# 3_valve.net
KiCad netlist of a schematic drawn in EAGLE
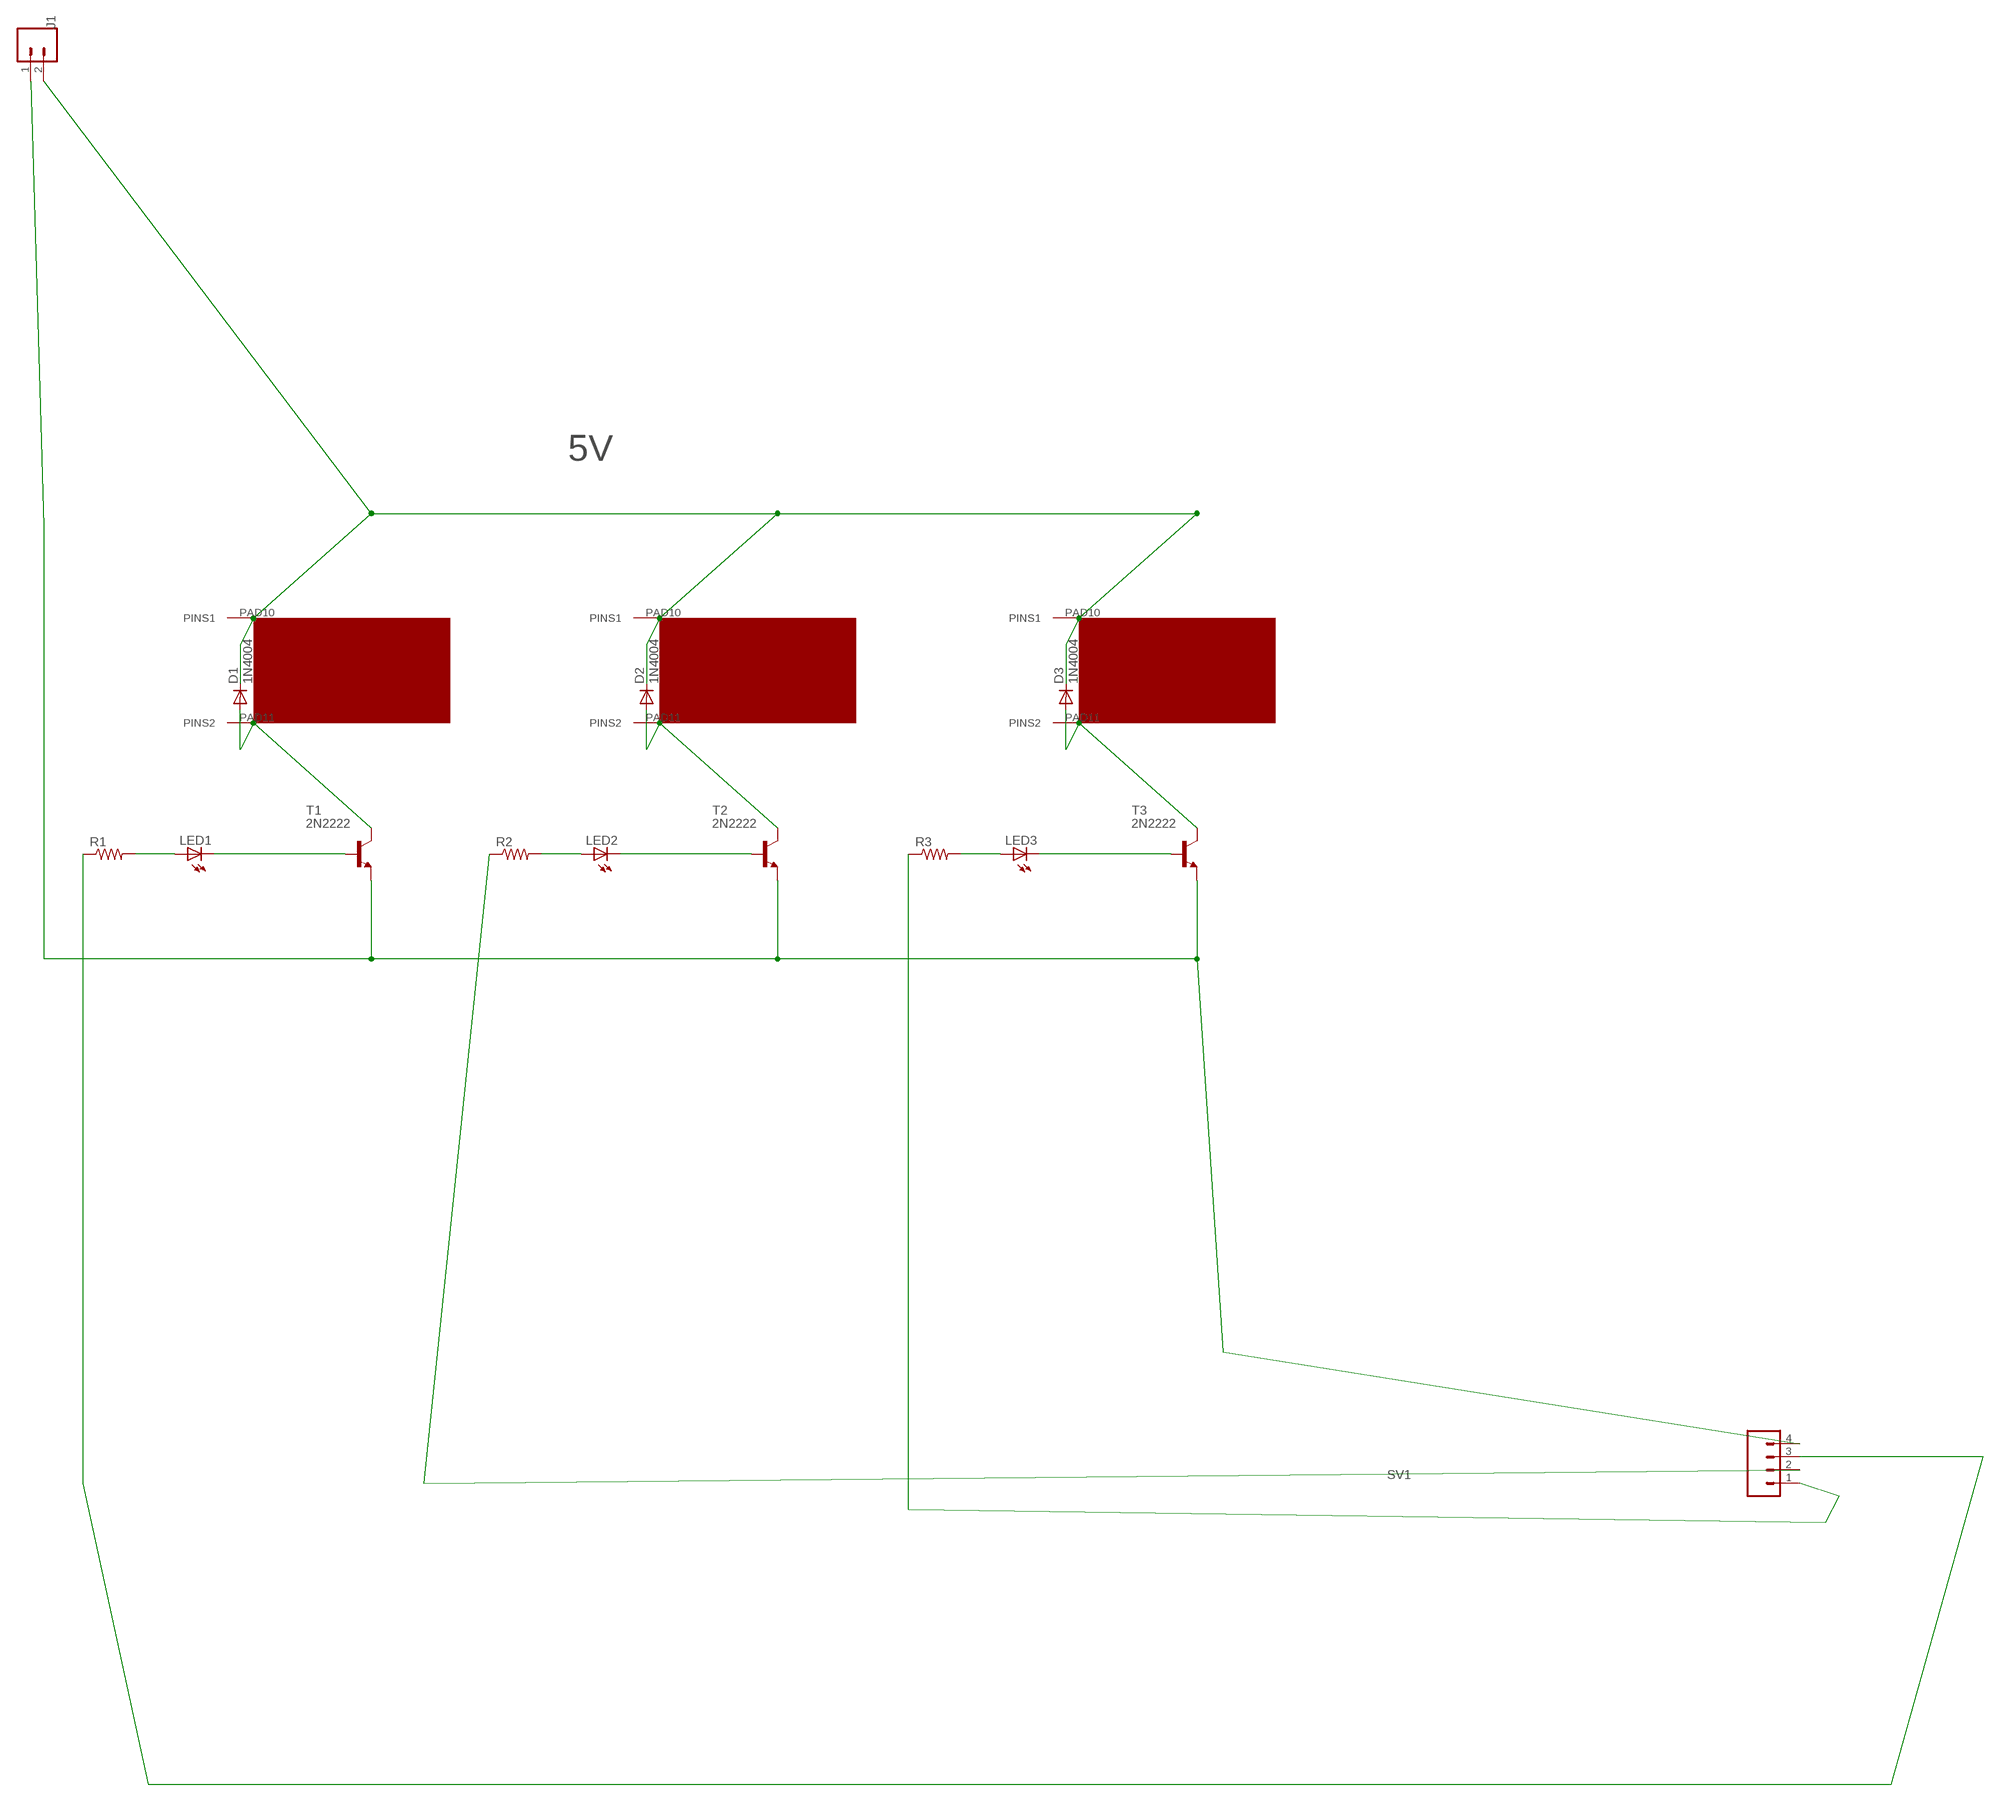
[diagram p0: schematic, sheet 1]

(export (version "E")
  (design (tool "Eeschema 10.0.6"))
  (components
    (comp (ref "D1")
      (value "1N4004")
      (footprint "eagle-import:DO41-10")
      (libsource (lib "eagle-import") (part "1N4004"))
    )
    (comp (ref "D2")
      (value "1N4004")
      (footprint "eagle-import:DO41-10")
      (libsource (lib "eagle-import") (part "1N4004"))
    )
    (comp (ref "D3")
      (value "1N4004")
      (footprint "eagle-import:DO41-10")
      (libsource (lib "eagle-import") (part "1N4004"))
    )
    (comp (ref "J1")
      (value "CONN_023.5MM")
      (footprint "eagle-import:SCREWTERMINAL-3.5MM-2")
      (libsource (lib "eagle-import") (part "CONN_023.5MM"))
    )
    (comp (ref "LED1")
      (value "LED5MM")
      (footprint "eagle-import:LED5MM")
      (libsource (lib "eagle-import") (part "LED5MM"))
    )
    (comp (ref "LED2")
      (value "LED5MM")
      (footprint "eagle-import:LED5MM")
      (libsource (lib "eagle-import") (part "LED5MM"))
    )
    (comp (ref "LED3")
      (value "LED5MM")
      (footprint "eagle-import:LED5MM")
      (libsource (lib "eagle-import") (part "LED5MM"))
    )
    (comp (ref "R1")
      (value "R-US_0207/10")
      (footprint "eagle-import:0207_10")
      (libsource (lib "eagle-import") (part "R-US_0207/10"))
    )
    (comp (ref "R2")
      (value "R-US_0207/10")
      (footprint "eagle-import:0207_10")
      (libsource (lib "eagle-import") (part "R-US_0207/10"))
    )
    (comp (ref "R3")
      (value "R-US_0207/10")
      (footprint "eagle-import:0207_10")
      (libsource (lib "eagle-import") (part "R-US_0207/10"))
    )
    (comp (ref "SV1")
      (value "CONN_04")
      (footprint "eagle-import:1X04")
      (libsource (lib "eagle-import") (part "CONN_04"))
    )
    (comp (ref "T1")
      (value "2N2222")
      (footprint "eagle-import:TO92-EBC-OVAL")
      (libsource (lib "eagle-import") (part "2N2222"))
    )
    (comp (ref "T2")
      (value "2N2222")
      (footprint "eagle-import:TO92-EBC-OVAL")
      (libsource (lib "eagle-import") (part "2N2222"))
    )
    (comp (ref "T3")
      (value "2N2222")
      (footprint "eagle-import:TO92-EBC-OVAL")
      (libsource (lib "eagle-import") (part "2N2222"))
    )
    (comp (ref "U$1")
      (value "VALVE")
      (footprint "eagle-import:VALVTEST2")
      (libsource (lib "eagle-import") (part "VALVE"))
    )
    (comp (ref "U$2")
      (value "VALVE")
      (footprint "eagle-import:VALVTEST2")
      (libsource (lib "eagle-import") (part "VALVE"))
    )
    (comp (ref "VALVE3")
      (value "VALVE")
      (footprint "eagle-import:VALVTEST2")
      (libsource (lib "eagle-import") (part "VALVE"))
    )
  )
  (nets
    (net (code "1") (name "/5V") (class "Default")
      (node (ref "D1") (pin "C") (pinfunction "C_C") (pintype "passive"))
      (node (ref "D2") (pin "C") (pinfunction "C_C") (pintype "passive"))
      (node (ref "D3") (pin "C") (pinfunction "C_C") (pintype "passive"))
      (node (ref "J1") (pin "2") (pinfunction "2_2") (pintype "passive"))
      (node (ref "U$1") (pin "PAD10") (pinfunction "PINS1_PAD10") (pintype "bidirectional"))
      (node (ref "U$2") (pin "PAD10") (pinfunction "PINS1_PAD10") (pintype "bidirectional"))
      (node (ref "VALVE3") (pin "PAD10") (pinfunction "PINS1_PAD10") (pintype "bidirectional"))
    )
    (net (code "2") (name "Net-(J1-Pad1)") (class "Default")
      (node (ref "J1") (pin "1") (pinfunction "1_1") (pintype "passive"))
      (node (ref "SV1") (pin "4") (pinfunction "4_4") (pintype "passive"))
      (node (ref "T1") (pin "E") (pinfunction "E_E") (pintype "passive"))
      (node (ref "T2") (pin "E") (pinfunction "E_E") (pintype "passive"))
      (node (ref "T3") (pin "E") (pinfunction "E_E") (pintype "passive"))
    )
    (net (code "3") (name "Net-(LED1-C)") (class "Default")
      (node (ref "LED1") (pin "K") (pinfunction "C_K") (pintype "passive"))
      (node (ref "T1") (pin "B") (pinfunction "B_B") (pintype "passive"))
    )
    (net (code "4") (name "Net-(LED1-PadA)") (class "Default")
      (node (ref "LED1") (pin "A") (pinfunction "A_A") (pintype "passive"))
      (node (ref "R1") (pin "2") (pinfunction "2_2") (pintype "passive"))
    )
    (net (code "5") (name "Net-(LED2-C)") (class "Default")
      (node (ref "LED2") (pin "K") (pinfunction "C_K") (pintype "passive"))
      (node (ref "T2") (pin "B") (pinfunction "B_B") (pintype "passive"))
    )
    (net (code "6") (name "Net-(LED2-PadA)") (class "Default")
      (node (ref "LED2") (pin "A") (pinfunction "A_A") (pintype "passive"))
      (node (ref "R2") (pin "2") (pinfunction "2_2") (pintype "passive"))
    )
    (net (code "7") (name "Net-(LED3-C)") (class "Default")
      (node (ref "LED3") (pin "K") (pinfunction "C_K") (pintype "passive"))
      (node (ref "T3") (pin "B") (pinfunction "B_B") (pintype "passive"))
    )
    (net (code "8") (name "Net-(LED3-PadA)") (class "Default")
      (node (ref "LED3") (pin "A") (pinfunction "A_A") (pintype "passive"))
      (node (ref "R3") (pin "2") (pinfunction "2_2") (pintype "passive"))
    )
    (net (code "9") (name "Net-(R1-Pad1)") (class "Default")
      (node (ref "R1") (pin "1") (pinfunction "1_1") (pintype "passive"))
      (node (ref "SV1") (pin "3") (pinfunction "3_3") (pintype "passive"))
    )
    (net (code "10") (name "Net-(R2-Pad1)") (class "Default")
      (node (ref "R2") (pin "1") (pinfunction "1_1") (pintype "passive"))
      (node (ref "SV1") (pin "2") (pinfunction "2_2") (pintype "passive"))
    )
    (net (code "11") (name "Net-(R3-Pad1)") (class "Default")
      (node (ref "R3") (pin "1") (pinfunction "1_1") (pintype "passive"))
      (node (ref "SV1") (pin "1") (pinfunction "1_1") (pintype "passive"))
    )
    (net (code "12") (name "Net-(U$1-PINS2)") (class "Default")
      (node (ref "D1") (pin "A") (pinfunction "A_A") (pintype "passive"))
      (node (ref "T1") (pin "C") (pinfunction "C_C") (pintype "passive"))
      (node (ref "U$1") (pin "PAD11") (pinfunction "PINS2_PAD11") (pintype "bidirectional"))
    )
    (net (code "13") (name "Net-(U$2-PINS2)") (class "Default")
      (node (ref "D2") (pin "A") (pinfunction "A_A") (pintype "passive"))
      (node (ref "T2") (pin "C") (pinfunction "C_C") (pintype "passive"))
      (node (ref "U$2") (pin "PAD11") (pinfunction "PINS2_PAD11") (pintype "bidirectional"))
    )
    (net (code "14") (name "Net-(VALVE3-PINS2)") (class "Default")
      (node (ref "D3") (pin "A") (pinfunction "A_A") (pintype "passive"))
      (node (ref "T3") (pin "C") (pinfunction "C_C") (pintype "passive"))
      (node (ref "VALVE3") (pin "PAD11") (pinfunction "PINS2_PAD11") (pintype "bidirectional"))
    )
  )
)
